# 105358-3SC001-03_CPU_BRD.net
KiCad netlist of a schematic drawn in Altium Designer
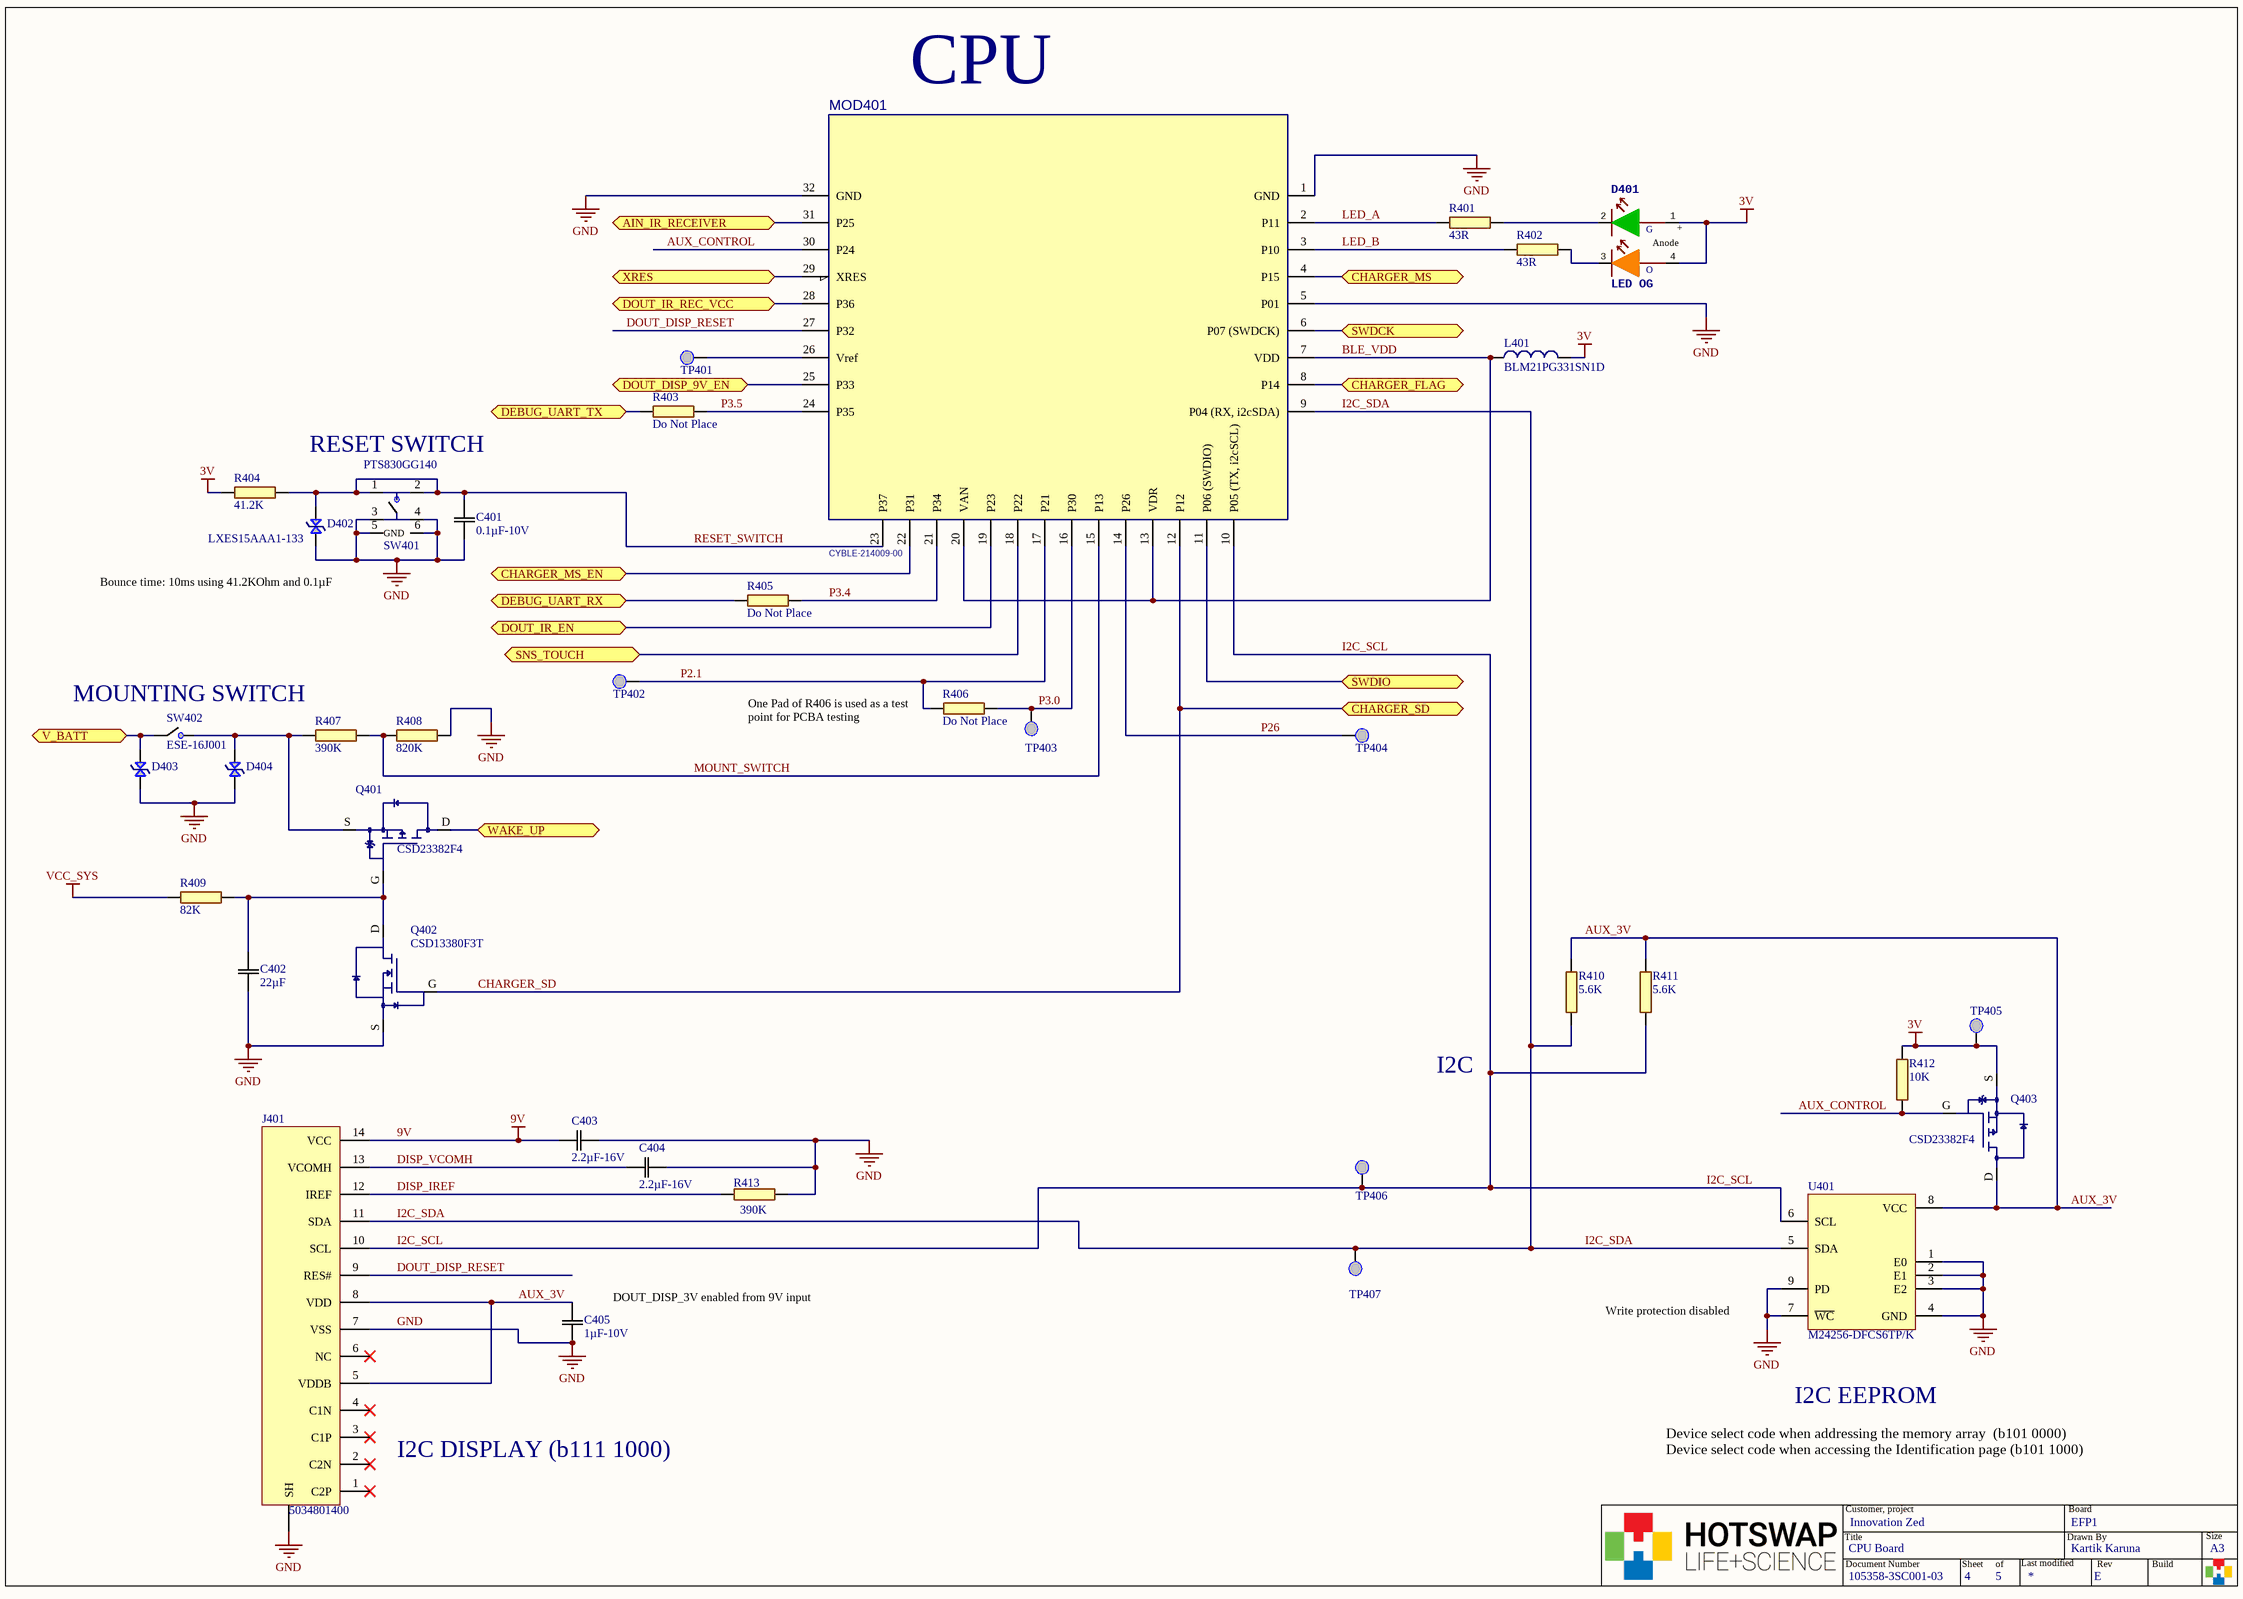
[diagram p0: 105358-3SC001-03_CPU_BRD.SchDoc]

(export (version "E")
  (design (tool "Eeschema 10.0.6"))
  (components
    (comp (ref "C401")
      (value "0.1µF-10V")
      (footprint "0402C_HIGH_DENSITY")
      (description "0.1µF ±10% 10V X5R Ceramic Capacitor 0402")
      (fields
        (field (name "MANUFACTURER PART NUMBER") "CC0402KRX5R6BB104")
        (field (name "MANUFACTURER") "Yageo")
      )
      (libsource (lib "ConnectMedical") (part "0402C-0.1uF-10V"))
    )
    (comp (ref "C402")
      (value "22µF")
      (footprint "0603C-GENERIC")
      (description "22µF ±20% 10V Ceramic Capacitor X5R 0603")
      (fields
        (field (name "MANUFACTURER PART NUMBER") "C1608X5R1A226M080AC")
        (field (name "MANUFACTURER") "TDK Corporation")
      )
      (libsource (lib "ConnectMedical") (part "0603C-22uF-10V"))
    )
    (comp (ref "C403")
      (value "2.2µF-16V")
      (footprint "0402C_HIGH_DENSITY")
      (description "CAP CER 2.2UF 16V X5R 0402")
      (fields
        (field (name "MANUFACTURER PART NUMBER") "GRM155R61C225KE44D")
        (field (name "MANUFACTURER") "Murata Electronics North America")
      )
      (libsource (lib "ConnectMedical") (part "0402C-2,2uF-16V"))
    )
    (comp (ref "C404")
      (value "2.2µF-16V")
      (footprint "0402C_HIGH_DENSITY")
      (description "CAP CER 2.2UF 16V X5R 0402")
      (fields
        (field (name "MANUFACTURER PART NUMBER") "GRM155R61C225KE44D")
        (field (name "MANUFACTURER") "Murata Electronics North America")
      )
      (libsource (lib "ConnectMedical") (part "0402C-2,2uF-16V"))
    )
    (comp (ref "C405")
      (value "1µF-10V")
      (footprint "0402C_HIGH_DENSITY")
      (description "1µF ±10% 10V X5R Ceramic Capacitor 0402")
      (fields
        (field (name "MANUFACTURER PART NUMBER") "CC0402KRX5R6BB105")
        (field (name "MANUFACTURER") "Yageo")
      )
      (libsource (lib "ConnectMedical") (part "0402C-1uF-10V"))
    )
    (comp (ref "D401")
      (value "LED OG")
      (footprint "KPHBM-2012CGKSEKC")
      (description "LED GRN/ORNG")
      (fields
        (field (name "MANUFACTURER") "Kingbright")
        (field (name "MANUFACTURER PART NUMBER") "KPHBM-2012CGKSEKC")
      )
      (libsource (lib "ConnectMedical") (part "LED GRN/ORNG 570NM 601NM"))
    )
    (comp (ref "D402")
      (value "LXES15AAA1-133")
      (footprint "0402C-GENERIC")
      (description "TVS DIODE 15VWM 0402")
      (fields
        (field (name "MANUFACTURER") "Murata Electronics North America")
        (field (name "DIGI-KEY PART NUMBER") "490-13209-1-ND")
      )
      (libsource (lib "ConnectMedical") (part "TVS DIODE 15VWM 0402"))
    )
    (comp (ref "D403")
      (value "LXES15AAA1-133")
      (footprint "0402C-GENERIC")
      (description "TVS DIODE 15VWM 0402")
      (fields
        (field (name "MANUFACTURER") "Murata Electronics North America")
        (field (name "DIGI-KEY PART NUMBER") "490-13209-1-ND")
      )
      (libsource (lib "ConnectMedical") (part "TVS DIODE 15VWM 0402"))
    )
    (comp (ref "D404")
      (value "LXES15AAA1-133")
      (footprint "0402C-GENERIC")
      (description "TVS DIODE 15VWM 0402")
      (fields
        (field (name "MANUFACTURER") "Murata Electronics North America")
        (field (name "DIGI-KEY PART NUMBER") "490-13209-1-ND")
      )
      (libsource (lib "ConnectMedical") (part "TVS DIODE 15VWM 0402"))
    )
    (comp (ref "J401")
      (value "5034801400")
      (footprint "5034801400")
      (description "Connector molex to OLED Display")
      (fields (field (name "MANUFACTURER") "Molex, LLC") (field (name "DIGI-KEY PART NUMBER") "WM1442CT-ND"))
      (libsource (lib "ConnectMedical") (part "Molex-5034801400"))
    )
    (comp (ref "L401")
      (value "BLM21PG331SN1D")
      (footprint "0805L_HIGH_DENSITY - Hybrid 0402")
      (description "0805 Ferrite Bead 330Ohm@100MHz")
      (fields
        (field (name "DIGI-KEY PART NUMBER") "490-5988-1-ND")
        (field (name "MANUFACTURER") "Murata Electronics North America")
      )
      (libsource (lib "ConnectMedical") (part "BLM21PG331SN1D"))
    )
    (comp (ref "MOD401")
      (value "CYBLE-214009-00")
      (footprint "CYBLE-014008-00_MinKeepOut")
      (description "BLE PSoC Module 4.1")
      (fields
        (field (name "MANUFACTURER") "Cypress Semiconductor Corp")
        (field (name "DIGI-KEY PART NUMBER") "428-3809-ND")
      )
      (libsource (lib "ConnectMedical") (part "CYBLE-214009-00"))
    )
    (comp (ref "Q401")
      (value "CSD23382F4")
      (footprint "CSD23382F4 -DFN65P100X35-3L")
      (description "MOSFET P-CH 12V 22A 3PICOSTAR")
      (fields
        (field (name "DIGI-KEY PART NUMBER") "296-40003-1-ND")
        (field (name "MANUFACTURER") "Texas Instruments")
      )
      (libsource (lib "ConnectMedical") (part "CSD23382F4"))
    )
    (comp (ref "Q402")
      (value "CSD13380F3T")
      (footprint "CSD13380F3-DFN40P69X35-3L")
      (description "12V N-CHANNEL FEMTOFET MOSFET")
      (fields (field (name "MANUFACTURER") "Texas Instruments"))
      (libsource (lib "ConnectMedical") (part "CSD13380F3T"))
    )
    (comp (ref "Q403")
      (value "CSD23382F4")
      (footprint "CSD23382F4 -DFN65P100X35-3L")
      (description "MOSFET P-CH 12V 22A 3PICOSTAR")
      (fields
        (field (name "DIGI-KEY PART NUMBER") "296-40003-1-ND")
        (field (name "MANUFACTURER") "Texas Instruments")
      )
      (libsource (lib "ConnectMedical") (part "CSD23382F4"))
    )
    (comp (ref "R401")
      (value "43R")
      (footprint "0402R-GENERIC")
      (description "RES SMD 43 OHM 5% 1/16W 0402")
      (fields (field (name "DIGI-KEY PART NUMBER") "311-43JRCT-ND") (field (name "MANUFACTURER") "Yageo"))
      (libsource (lib "ConnectMedical") (part "0402R- 43 OHM-1%-0.063W"))
    )
    (comp (ref "R402")
      (value "43R")
      (footprint "0402R-GENERIC")
      (description "RES SMD 43 OHM 5% 1/16W 0402")
      (fields (field (name "DIGI-KEY PART NUMBER") "311-43JRCT-ND") (field (name "MANUFACTURER") "Yageo"))
      (libsource (lib "ConnectMedical") (part "0402R- 43 OHM-1%-0.063W"))
    )
    (comp (ref "R403")
      (value "Do Not Place")
      (footprint "0402R-GENERIC - DNP")
      (libsource (lib "ConnectMedical") (part "0402R-Do Not Place"))
    )
    (comp (ref "R404")
      (value "41.2K")
      (footprint "0402R-GENERIC")
      (description "RES SMD 41.2kOHM 1% 1/16W 0402")
      (fields (field (name "DIGI-KEY PART NUMBER") "YAG3155CT-ND") (field (name "MANUFACTURER") "Yageo"))
      (libsource (lib "ConnectMedical") (part "0402R-41.2k OHM-1%-0.063W"))
    )
    (comp (ref "R405")
      (value "Do Not Place")
      (footprint "0402R-GENERIC - DNP")
      (libsource (lib "ConnectMedical") (part "0402R-Do Not Place"))
    )
    (comp (ref "R406")
      (value "Do Not Place")
      (footprint "0402R-GENERIC - DNP")
      (libsource (lib "ConnectMedical") (part "0402R-Do Not Place"))
    )
    (comp (ref "R407")
      (value "390K")
      (footprint "0402R-GENERIC")
      (description "RES SMD 390kOHM 1% 1/16W 0402")
      (fields (field (name "DIGI-KEY PART NUMBER") "YAG3143CT-ND") (field (name "MANUFACTURER") "Yageo"))
      (libsource (lib "ConnectMedical") (part "0402R-390k OHM-1%-0.063W"))
    )
    (comp (ref "R408")
      (value "820K")
      (footprint "0402R-GENERIC")
      (description "RES SMD 820kOHM 1% 1/16W 0402")
      (fields (field (name "DIGI-KEY PART NUMBER") "YAG3240CT-ND") (field (name "MANUFACTURER") "Yageo"))
      (libsource (lib "ConnectMedical") (part "0402R-820k OHM-1%-0.063W"))
    )
    (comp (ref "R409")
      (value "82K")
      (footprint "0402R-GENERIC")
      (description "RES SMD 82kOHM 1% 1/16W 0402")
      (fields (field (name "DIGI-KEY PART NUMBER") "311-82.0KLRCT-ND") (field (name "MANUFACTURER") "Yageo"))
      (libsource (lib "ConnectMedical") (part "0402R-82k OHM-1%-0.063W"))
    )
    (comp (ref "R410")
      (value "5.6K")
      (footprint "0402R-GENERIC")
      (description "RES SMD 5.6kOHM 5% 1/16W 0402")
      (fields (field (name "DIGI-KEY PART NUMBER") "311-5.6KJRCT-ND") (field (name "MANUFACTURER") "Yageo"))
      (libsource (lib "ConnectMedical") (part "0402R-5.6k OHM-5%-0.063W"))
    )
    (comp (ref "R411")
      (value "5.6K")
      (footprint "0402R-GENERIC")
      (description "RES SMD 5.6kOHM 5% 1/16W 0402")
      (fields (field (name "DIGI-KEY PART NUMBER") "311-5.6KJRCT-ND") (field (name "MANUFACTURER") "Yageo"))
      (libsource (lib "ConnectMedical") (part "0402R-5.6k OHM-5%-0.063W"))
    )
    (comp (ref "R412")
      (value "10K")
      (footprint "0402R-GENERIC")
      (description "RES SMD 10kOHM 1% 1/16W 0402")
      (fields (field (name "DIGI-KEY PART NUMBER") "311-10.0KLRCT-ND") (field (name "MANUFACTURER") "Yageo"))
      (libsource (lib "ConnectMedical") (part "0402R-10k OHM-1%-0.063W"))
    )
    (comp (ref "R413")
      (value "390K")
      (footprint "0402R-GENERIC")
      (description "RES SMD 390kOHM 1% 1/16W 0402")
      (fields (field (name "DIGI-KEY PART NUMBER") "YAG3143CT-ND") (field (name "MANUFACTURER") "Yageo"))
      (libsource (lib "ConnectMedical") (part "0402R-390k OHM-1%-0.063W"))
    )
    (comp (ref "SW401")
      (value "PTS830GG140")
      (footprint "PTS830GG140GSMTRLFS")
      (description "SPST Tactile Switch")
      (fields
        (field (name "MANUFACTURER PART NUMBER") "PTS830GG140G SMTR LFS")
        (field (name "MANUFACTURER") "C&K")
      )
      (libsource (lib "ConnectMedical") (part "PTS830GG140"))
    )
    (comp (ref "SW402")
      (value "ESE-16J001")
      (footprint "ESE-16J001")
      (description "SWITCH DETECTOR SPST-NO 10MA 5V")
      (fields
        (field (name "MANUFACTURER") "Panasonic Electronic Components")
        (field (name "DIGI-KEY PART NUMBER") "P14266SCT-ND")
      )
      (libsource (lib "ConnectMedical") (part "ESE-16J001"))
    )
    (comp (ref "TP401")
      (value "TEST POINT")
      (footprint "PAD TEST POINT")
      (description "Testing Poiny")
      (libsource (lib "ConnectMedical") (part "TEST POINT"))
    )
    (comp (ref "TP402")
      (value "TEST POINT")
      (footprint "PAD TEST POINT")
      (description "Testing Poiny")
      (libsource (lib "ConnectMedical") (part "TEST POINT"))
    )
    (comp (ref "TP403")
      (value "TEST POINT")
      (footprint "PAD TEST POINT")
      (description "Testing Poiny")
      (libsource (lib "ConnectMedical") (part "TEST POINT"))
    )
    (comp (ref "TP404")
      (value "TEST POINT")
      (footprint "PAD TEST POINT")
      (description "Testing Poiny")
      (libsource (lib "ConnectMedical") (part "TEST POINT"))
    )
    (comp (ref "TP405")
      (value "TEST POINT")
      (footprint "PAD TEST POINT")
      (description "Testing Poiny")
      (libsource (lib "ConnectMedical") (part "TEST POINT"))
    )
    (comp (ref "TP406")
      (value "TEST POINT")
      (footprint "PAD TEST POINT")
      (description "Testing Poiny")
      (libsource (lib "ConnectMedical") (part "TEST POINT"))
    )
    (comp (ref "TP407")
      (value "TEST POINT")
      (footprint "PAD TEST POINT")
      (description "Testing Poiny")
      (libsource (lib "ConnectMedical") (part "TEST POINT"))
    )
    (comp (ref "U401")
      (value "M24256-DFCS6TP/K")
      (footprint "UFDFPN8-M24256-DFMC6TG")
      (description "IC EEPROM 256KBIT 400KHZ 8UFDFPN")
      (fields
        (field (name "MANUFACTURER PART NUMBER") "M24256-DFMC6TG")
        (field (name "MANUFACTURER") "STMicroelectronics")
      )
      (libsource (lib "ConnectMedical") (part "M24256-DFMC6TG"))
    )
  )
  (nets
    (net (code "1") (name "/AIN_IR_RECEIVER") (class "Default")
      (node (ref "MOD401") (pin "31") (pinfunction "P25_31") (pintype "passive"))
    )
    (net (code "2") (name "/AUX_3V") (class "Default")
      (node (ref "C405") (pin "2") (pinfunction "2_2") (pintype "passive"))
      (node (ref "J401") (pin "5") (pinfunction "VDDB_5") (pintype "passive"))
      (node (ref "J401") (pin "8") (pinfunction "VDD_8") (pintype "passive"))
      (node (ref "Q403") (pin "D") (pinfunction "3_D") (pintype "passive"))
      (node (ref "R410") (pin "1") (pintype "passive"))
      (node (ref "R411") (pin "1") (pintype "passive"))
      (node (ref "U401") (pin "8") (pinfunction "VCC_8") (pintype "passive"))
    )
    (net (code "3") (name "/AUX_CONTROL") (class "Default")
      (node (ref "MOD401") (pin "30") (pinfunction "P24_30") (pintype "passive"))
      (node (ref "Q403") (pin "G") (pinfunction "1_G") (pintype "passive"))
      (node (ref "R412") (pin "2") (pintype "passive"))
    )
    (net (code "4") (name "/BLE_VDD") (class "Default")
      (node (ref "L401") (pin "1") (pinfunction "1_1") (pintype "passive"))
      (node (ref "MOD401") (pin "13") (pinfunction "VDR_13") (pintype "power_in"))
      (node (ref "MOD401") (pin "20") (pinfunction "VAN_20") (pintype "power_in"))
      (node (ref "MOD401") (pin "7") (pinfunction "VDD_7") (pintype "power_in"))
    )
    (net (code "5") (name "/CHARGER_FLAG") (class "Default")
      (node (ref "MOD401") (pin "8") (pinfunction "P14_8") (pintype "passive"))
    )
    (net (code "6") (name "/CHARGER_MS") (class "Default")
      (node (ref "MOD401") (pin "4") (pinfunction "P15_4") (pintype "passive"))
    )
    (net (code "7") (name "/CHARGER_MS_EN") (class "Default")
      (node (ref "MOD401") (pin "22") (pinfunction "P31_22") (pintype "passive"))
    )
    (net (code "8") (name "/CHARGER_SD") (class "Default")
      (node (ref "MOD401") (pin "12") (pinfunction "P12_12") (pintype "passive"))
      (node (ref "Q402") (pin "G") (pinfunction "1_G") (pintype "passive"))
    )
    (net (code "9") (name "/DEBUG_UART_RX") (class "Default")
      (node (ref "R405") (pin "1") (pintype "passive"))
    )
    (net (code "10") (name "/DEBUG_UART_TX") (class "Default")
      (node (ref "R403") (pin "1") (pintype "passive"))
    )
    (net (code "11") (name "/DISP_IREF") (class "Default")
      (node (ref "J401") (pin "12") (pinfunction "IREF_12") (pintype "passive"))
      (node (ref "R413") (pin "1") (pintype "passive"))
    )
    (net (code "12") (name "/DISP_VCOMH") (class "Default")
      (node (ref "C404") (pin "2") (pinfunction "2_2") (pintype "passive"))
      (node (ref "J401") (pin "13") (pinfunction "VCOMH_13") (pintype "passive"))
    )
    (net (code "13") (name "/DOUT_DISP_9V_EN") (class "Default")
      (node (ref "MOD401") (pin "25") (pinfunction "P33_25") (pintype "passive"))
    )
    (net (code "14") (name "/DOUT_DISP_RESET") (class "Default")
      (node (ref "J401") (pin "9") (pinfunction "RES#_9") (pintype "passive"))
      (node (ref "MOD401") (pin "27") (pinfunction "P32_27") (pintype "passive"))
    )
    (net (code "15") (name "/DOUT_IR_EN") (class "Default")
      (node (ref "MOD401") (pin "19") (pinfunction "P23_19") (pintype "passive"))
    )
    (net (code "16") (name "/DOUT_IR_REC_VCC") (class "Default")
      (node (ref "MOD401") (pin "28") (pinfunction "P36_28") (pintype "passive"))
    )
    (net (code "17") (name "/I2C_SCL") (class "Default")
      (node (ref "J401") (pin "10") (pinfunction "SCL_10") (pintype "passive"))
      (node (ref "MOD401") (pin "10") (pinfunction "P05_(TX,_i2cSCL)_10") (pintype "passive"))
      (node (ref "R411") (pin "2") (pintype "passive"))
      (node (ref "TP406") (pin "1") (pinfunction "Test_Point_1") (pintype "passive"))
      (node (ref "U401") (pin "6") (pinfunction "SCL_6") (pintype "passive"))
    )
    (net (code "18") (name "/I2C_SDA") (class "Default")
      (node (ref "J401") (pin "11") (pinfunction "SDA_11") (pintype "passive"))
      (node (ref "MOD401") (pin "9") (pinfunction "P04_(RX,_i2cSDA)_9") (pintype "passive"))
      (node (ref "R410") (pin "2") (pintype "passive"))
      (node (ref "TP407") (pin "1") (pinfunction "Test_Point_1") (pintype "passive"))
      (node (ref "U401") (pin "5") (pinfunction "SDA_5") (pintype "passive"))
    )
    (net (code "19") (name "/LED_A") (class "Default")
      (node (ref "MOD401") (pin "2") (pinfunction "P11_2") (pintype "passive"))
      (node (ref "R401") (pin "1") (pintype "passive"))
    )
    (net (code "20") (name "/LED_B") (class "Default")
      (node (ref "MOD401") (pin "3") (pinfunction "P10_3") (pintype "passive"))
      (node (ref "R402") (pin "1") (pintype "passive"))
    )
    (net (code "21") (name "/MOUNT_SWITCH") (class "Default")
      (node (ref "MOD401") (pin "15") (pinfunction "P13_15") (pintype "passive"))
      (node (ref "R407") (pin "2") (pintype "passive"))
      (node (ref "R408") (pin "2") (pintype "passive"))
    )
    (net (code "22") (name "/P2.1") (class "Default")
      (node (ref "MOD401") (pin "17") (pinfunction "P21_17") (pintype "passive"))
      (node (ref "R406") (pin "1") (pintype "passive"))
      (node (ref "TP402") (pin "1") (pinfunction "Test_Point_1") (pintype "passive"))
    )
    (net (code "23") (name "/P3.0") (class "Default")
      (node (ref "MOD401") (pin "16") (pinfunction "P30_16") (pintype "passive"))
      (node (ref "R406") (pin "2") (pintype "passive"))
      (node (ref "TP403") (pin "1") (pinfunction "Test_Point_1") (pintype "passive"))
    )
    (net (code "24") (name "/P3.4") (class "Default")
      (node (ref "MOD401") (pin "21") (pinfunction "P34_21") (pintype "passive"))
      (node (ref "R405") (pin "2") (pintype "passive"))
    )
    (net (code "25") (name "/P3.5") (class "Default")
      (node (ref "MOD401") (pin "24") (pinfunction "P35_24") (pintype "passive"))
      (node (ref "R403") (pin "2") (pintype "passive"))
    )
    (net (code "26") (name "/P26") (class "Default")
      (node (ref "MOD401") (pin "14") (pinfunction "P26_14") (pintype "passive"))
      (node (ref "TP404") (pin "1") (pinfunction "Test_Point_1") (pintype "passive"))
    )
    (net (code "27") (name "/RESET_SWITCH") (class "Default")
      (node (ref "C401") (pin "2") (pinfunction "2_2") (pintype "passive"))
      (node (ref "D402") (pin "2") (pinfunction "2_2") (pintype "passive"))
      (node (ref "MOD401") (pin "23") (pinfunction "P37_23") (pintype "passive"))
      (node (ref "R404") (pin "2") (pintype "passive"))
      (node (ref "SW401") (pin "1") (pinfunction "1_1") (pintype "passive"))
      (node (ref "SW401") (pin "2") (pinfunction "2_2") (pintype "passive"))
    )
    (net (code "28") (name "/SNS_TOUCH") (class "Default")
      (node (ref "MOD401") (pin "18") (pinfunction "P22_18") (pintype "passive"))
    )
    (net (code "29") (name "/SWDCK") (class "Default")
      (node (ref "MOD401") (pin "6") (pinfunction "P07_(SWDCK)_6") (pintype "passive"))
    )
    (net (code "30") (name "/SWDIO") (class "Default")
      (node (ref "MOD401") (pin "11") (pinfunction "P06_(SWDIO)_11") (pintype "passive"))
    )
    (net (code "31") (name "/V_BATT") (class "Default")
      (node (ref "D403") (pin "2") (pinfunction "2_2") (pintype "passive"))
      (node (ref "SW402") (pin "1") (pinfunction "1_1") (pintype "passive"))
    )
    (net (code "32") (name "/WAKE_UP") (class "Default")
      (node (ref "Q401") (pin "D") (pinfunction "3_D") (pintype "passive"))
    )
    (net (code "33") (name "/XRES") (class "Default")
      (node (ref "MOD401") (pin "29") (pinfunction "XRES_29") (pintype "passive"))
    )
    (net (code "34") (name "3V") (class "Default")
      (node (ref "D401") (pin "1") (pinfunction "1_1") (pintype "passive"))
      (node (ref "D401") (pin "4") (pinfunction "4_4") (pintype "passive"))
      (node (ref "L401") (pin "2") (pinfunction "2_2") (pintype "passive"))
      (node (ref "Q403") (pin "S") (pinfunction "2_S") (pintype "passive"))
      (node (ref "R404") (pin "1") (pintype "passive"))
      (node (ref "R412") (pin "1") (pintype "passive"))
      (node (ref "TP405") (pin "1") (pinfunction "Test_Point_1") (pintype "passive"))
    )
    (net (code "35") (name "9V") (class "Default")
      (node (ref "C403") (pin "1") (pinfunction "1_1") (pintype "passive"))
      (node (ref "J401") (pin "14") (pinfunction "VCC_14") (pintype "passive"))
    )
    (net (code "36") (name "GND") (class "Default")
      (node (ref "C401") (pin "1") (pinfunction "1_1") (pintype "passive"))
      (node (ref "C402") (pin "1") (pinfunction "1_1") (pintype "passive"))
      (node (ref "C403") (pin "2") (pinfunction "2_2") (pintype "passive"))
      (node (ref "C404") (pin "1") (pinfunction "1_1") (pintype "passive"))
      (node (ref "C405") (pin "1") (pinfunction "1_1") (pintype "passive"))
      (node (ref "D402") (pin "1") (pinfunction "1_1") (pintype "passive"))
      (node (ref "D403") (pin "1") (pinfunction "1_1") (pintype "passive"))
      (node (ref "D404") (pin "1") (pinfunction "1_1") (pintype "passive"))
      (node (ref "J401") (pin "7") (pinfunction "VSS_7") (pintype "power_in"))
      (node (ref "J401") (pin "SH") (pinfunction "SH_SH") (pintype "passive"))
      (node (ref "MOD401") (pin "1") (pinfunction "GND_1") (pintype "power_in"))
      (node (ref "MOD401") (pin "32") (pinfunction "GND_32") (pintype "power_in"))
      (node (ref "MOD401") (pin "5") (pinfunction "P01_5") (pintype "passive"))
      (node (ref "Q402") (pin "S") (pinfunction "2_S") (pintype "passive"))
      (node (ref "R408") (pin "1") (pintype "passive"))
      (node (ref "R413") (pin "2") (pintype "passive"))
      (node (ref "SW401") (pin "3") (pinfunction "3_3") (pintype "power_in"))
      (node (ref "SW401") (pin "4") (pinfunction "4_4") (pintype "power_in"))
      (node (ref "SW401") (pin "5") (pinfunction "5_5") (pintype "power_in"))
      (node (ref "SW401") (pin "6") (pinfunction "GND_6") (pintype "power_in"))
      (node (ref "U401") (pin "1") (pinfunction "E0_1") (pintype "passive"))
      (node (ref "U401") (pin "2") (pinfunction "E1_2") (pintype "passive"))
      (node (ref "U401") (pin "3") (pinfunction "E2_3") (pintype "passive"))
      (node (ref "U401") (pin "4") (pinfunction "GND_4") (pintype "passive"))
      (node (ref "U401") (pin "7") (pinfunction "~{WC}_7") (pintype "passive"))
      (node (ref "U401") (pin "9") (pinfunction "PD_9") (pintype "passive"))
    )
    (net (code "37") (name "Net-(D401-G)") (class "Default")
      (node (ref "D401") (pin "2") (pinfunction "G_2") (pintype "passive"))
      (node (ref "R401") (pin "2") (pintype "passive"))
    )
    (net (code "38") (name "Net-(D401-Pad3)") (class "Default")
      (node (ref "D401") (pin "3") (pinfunction "3_3") (pintype "passive"))
      (node (ref "R402") (pin "2") (pintype "passive"))
    )
    (net (code "39") (name "Net-(MOD401-Vref)") (class "Default")
      (node (ref "MOD401") (pin "26") (pinfunction "Vref_26") (pintype "power_in"))
      (node (ref "TP401") (pin "1") (pinfunction "Test_Point_1") (pintype "passive"))
    )
    (net (code "40") (name "Net-(Q401-1)") (class "Default")
      (node (ref "C402") (pin "2") (pinfunction "2_2") (pintype "passive"))
      (node (ref "Q401") (pin "G") (pinfunction "1_G") (pintype "passive"))
      (node (ref "Q402") (pin "D") (pinfunction "3_D") (pintype "passive"))
      (node (ref "R409") (pin "2") (pintype "passive"))
    )
    (net (code "41") (name "Net-(Q401-2)") (class "Default")
      (node (ref "D404") (pin "2") (pinfunction "2_2") (pintype "passive"))
      (node (ref "Q401") (pin "S") (pinfunction "2_S") (pintype "passive"))
      (node (ref "R407") (pin "1") (pintype "passive"))
      (node (ref "SW402") (pin "3") (pinfunction "3_3") (pintype "passive"))
    )
    (net (code "42") (name "VCC_SYS") (class "Default") (node (ref "R409") (pin "1") (pintype "passive")))
    (net (code "43") (name "unconnected-(J401-C1N-Pad4)") (class "Default")
      (node (ref "J401") (pin "4") (pinfunction "C1N_4") (pintype "passive+no_connect"))
    )
    (net (code "44") (name "unconnected-(J401-C1P-Pad3)") (class "Default")
      (node (ref "J401") (pin "3") (pinfunction "C1P_3") (pintype "passive+no_connect"))
    )
    (net (code "45") (name "unconnected-(J401-C2N-Pad2)") (class "Default")
      (node (ref "J401") (pin "2") (pinfunction "C2N_2") (pintype "passive+no_connect"))
    )
    (net (code "46") (name "unconnected-(J401-C2P-Pad1)") (class "Default")
      (node (ref "J401") (pin "1") (pinfunction "C2P_1") (pintype "passive+no_connect"))
    )
    (net (code "47") (name "unconnected-(J401-NC-Pad6)") (class "Default")
      (node (ref "J401") (pin "6") (pinfunction "NC_6") (pintype "passive+no_connect"))
    )
  )
)
